# lcd20x4_right.net
KiCad netlist of a schematic drawn in EAGLE
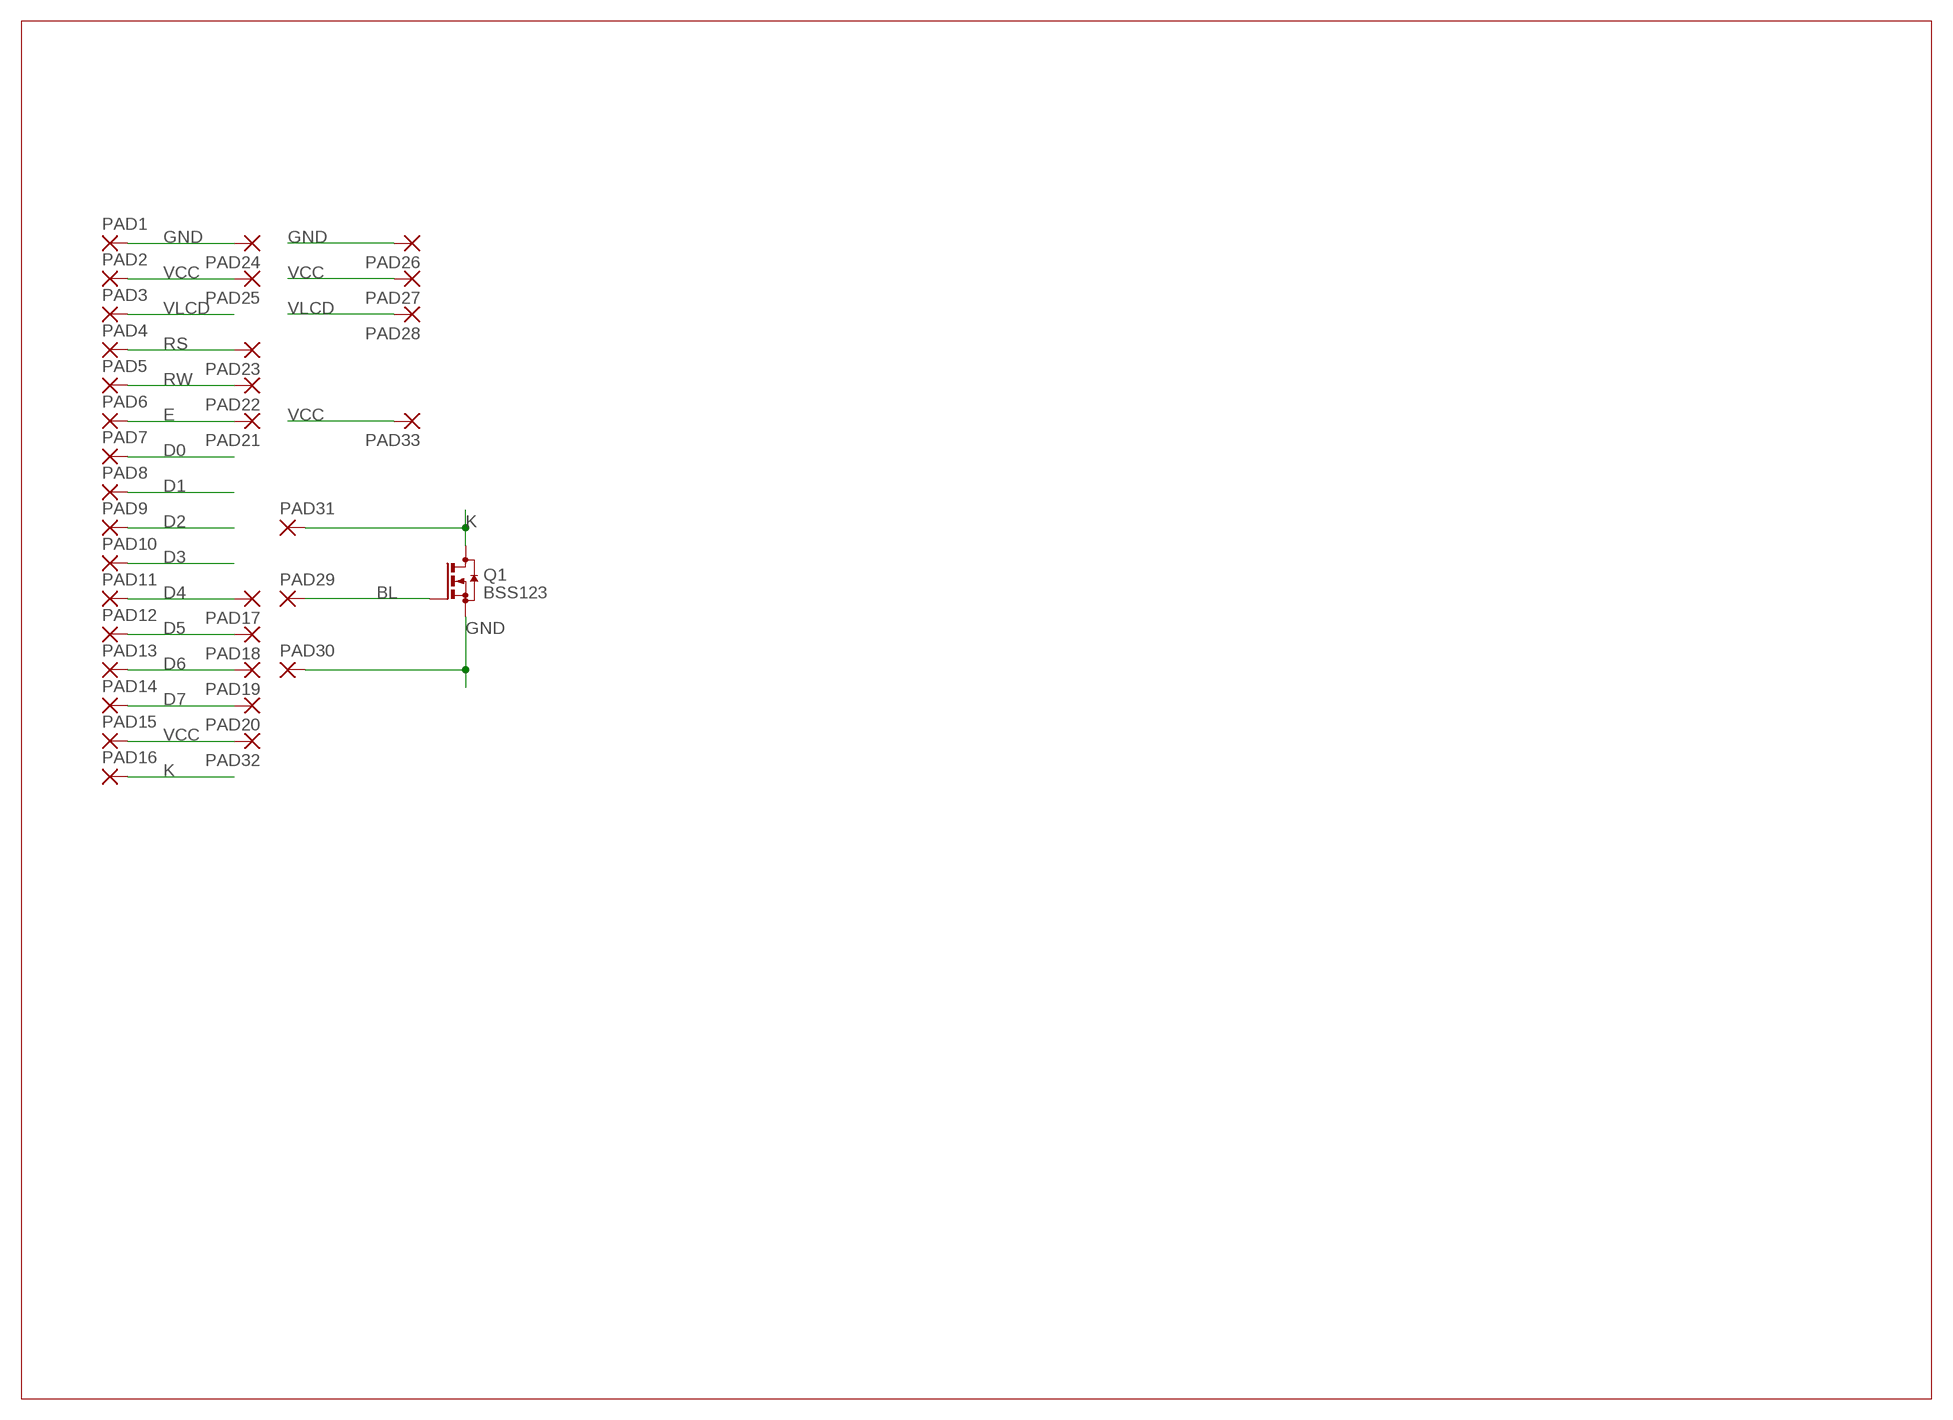
[diagram p0: schematic, sheet 1]

(export (version "E")
  (design (tool "Eeschema 10.0.6"))
  (components
    (comp (ref "PAD1")
      (value "WIREPAD1,6/0,8")
      (footprint "eagle-import:1,6_0,8")
      (libsource (lib "eagle-import") (part "WIREPAD1,6/0,8"))
    )
    (comp (ref "PAD2")
      (value "WIREPAD1,6/0,8")
      (footprint "eagle-import:1,6_0,8")
      (libsource (lib "eagle-import") (part "WIREPAD1,6/0,8"))
    )
    (comp (ref "PAD3")
      (value "WIREPAD1,6/0,8")
      (footprint "eagle-import:1,6_0,8")
      (libsource (lib "eagle-import") (part "WIREPAD1,6/0,8"))
    )
    (comp (ref "PAD4")
      (value "WIREPAD1,6/0,8")
      (footprint "eagle-import:1,6_0,8")
      (libsource (lib "eagle-import") (part "WIREPAD1,6/0,8"))
    )
    (comp (ref "PAD5")
      (value "WIREPAD1,6/0,8")
      (footprint "eagle-import:1,6_0,8")
      (libsource (lib "eagle-import") (part "WIREPAD1,6/0,8"))
    )
    (comp (ref "PAD6")
      (value "WIREPAD1,6/0,8")
      (footprint "eagle-import:1,6_0,8")
      (libsource (lib "eagle-import") (part "WIREPAD1,6/0,8"))
    )
    (comp (ref "PAD7")
      (value "WIREPAD1,6/0,8")
      (footprint "eagle-import:1,6_0,8")
      (libsource (lib "eagle-import") (part "WIREPAD1,6/0,8"))
    )
    (comp (ref "PAD8")
      (value "WIREPAD1,6/0,8")
      (footprint "eagle-import:1,6_0,8")
      (libsource (lib "eagle-import") (part "WIREPAD1,6/0,8"))
    )
    (comp (ref "PAD9")
      (value "WIREPAD1,6/0,8")
      (footprint "eagle-import:1,6_0,8")
      (libsource (lib "eagle-import") (part "WIREPAD1,6/0,8"))
    )
    (comp (ref "PAD10")
      (value "WIREPAD1,6/0,8")
      (footprint "eagle-import:1,6_0,8")
      (libsource (lib "eagle-import") (part "WIREPAD1,6/0,8"))
    )
    (comp (ref "PAD11")
      (value "WIREPAD1,6/0,8")
      (footprint "eagle-import:1,6_0,8")
      (libsource (lib "eagle-import") (part "WIREPAD1,6/0,8"))
    )
    (comp (ref "PAD12")
      (value "WIREPAD1,6/0,8")
      (footprint "eagle-import:1,6_0,8")
      (libsource (lib "eagle-import") (part "WIREPAD1,6/0,8"))
    )
    (comp (ref "PAD13")
      (value "WIREPAD1,6/0,8")
      (footprint "eagle-import:1,6_0,8")
      (libsource (lib "eagle-import") (part "WIREPAD1,6/0,8"))
    )
    (comp (ref "PAD14")
      (value "WIREPAD1,6/0,8")
      (footprint "eagle-import:1,6_0,8")
      (libsource (lib "eagle-import") (part "WIREPAD1,6/0,8"))
    )
    (comp (ref "PAD15")
      (value "WIREPAD1,6/0,8")
      (footprint "eagle-import:1,6_0,8")
      (libsource (lib "eagle-import") (part "WIREPAD1,6/0,8"))
    )
    (comp (ref "PAD16")
      (value "WIREPAD1,6/0,8")
      (footprint "eagle-import:1,6_0,8")
      (libsource (lib "eagle-import") (part "WIREPAD1,6/0,8"))
    )
    (comp (ref "PAD17")
      (value "WIREPAD1,6/0,8")
      (footprint "eagle-import:1,6_0,8")
      (libsource (lib "eagle-import") (part "WIREPAD1,6/0,8"))
    )
    (comp (ref "PAD18")
      (value "WIREPAD1,6/0,8")
      (footprint "eagle-import:1,6_0,8")
      (libsource (lib "eagle-import") (part "WIREPAD1,6/0,8"))
    )
    (comp (ref "PAD19")
      (value "WIREPAD1,6/0,8")
      (footprint "eagle-import:1,6_0,8")
      (libsource (lib "eagle-import") (part "WIREPAD1,6/0,8"))
    )
    (comp (ref "PAD20")
      (value "WIREPAD1,6/0,8")
      (footprint "eagle-import:1,6_0,8")
      (libsource (lib "eagle-import") (part "WIREPAD1,6/0,8"))
    )
    (comp (ref "PAD21")
      (value "WIREPAD1,6/0,8")
      (footprint "eagle-import:1,6_0,8")
      (libsource (lib "eagle-import") (part "WIREPAD1,6/0,8"))
    )
    (comp (ref "PAD22")
      (value "WIREPAD1,6/0,8")
      (footprint "eagle-import:1,6_0,8")
      (libsource (lib "eagle-import") (part "WIREPAD1,6/0,8"))
    )
    (comp (ref "PAD23")
      (value "WIREPAD1,6/0,8")
      (footprint "eagle-import:1,6_0,8")
      (libsource (lib "eagle-import") (part "WIREPAD1,6/0,8"))
    )
    (comp (ref "PAD24")
      (value "WIREPAD1,6/0,8")
      (footprint "eagle-import:1,6_0,8")
      (libsource (lib "eagle-import") (part "WIREPAD1,6/0,8"))
    )
    (comp (ref "PAD25")
      (value "WIREPAD1,6/0,8")
      (footprint "eagle-import:1,6_0,8")
      (libsource (lib "eagle-import") (part "WIREPAD1,6/0,8"))
    )
    (comp (ref "PAD26")
      (value "WIREPAD1,6/0,8")
      (footprint "eagle-import:1,6_0,8")
      (libsource (lib "eagle-import") (part "WIREPAD1,6/0,8"))
    )
    (comp (ref "PAD27")
      (value "WIREPAD1,6/0,8")
      (footprint "eagle-import:1,6_0,8")
      (libsource (lib "eagle-import") (part "WIREPAD1,6/0,8"))
    )
    (comp (ref "PAD28")
      (value "WIREPAD1,6/0,8")
      (footprint "eagle-import:1,6_0,8")
      (libsource (lib "eagle-import") (part "WIREPAD1,6/0,8"))
    )
    (comp (ref "PAD29")
      (value "WIREPAD1,6/0,8")
      (footprint "eagle-import:1,6_0,8")
      (libsource (lib "eagle-import") (part "WIREPAD1,6/0,8"))
    )
    (comp (ref "PAD30")
      (value "WIREPAD1,6/0,8")
      (footprint "eagle-import:1,6_0,8")
      (libsource (lib "eagle-import") (part "WIREPAD1,6/0,8"))
    )
    (comp (ref "PAD31")
      (value "WIREPAD1,6/0,8")
      (footprint "eagle-import:1,6_0,8")
      (libsource (lib "eagle-import") (part "WIREPAD1,6/0,8"))
    )
    (comp (ref "PAD32")
      (value "WIREPAD1,6/0,8")
      (footprint "eagle-import:1,6_0,8")
      (libsource (lib "eagle-import") (part "WIREPAD1,6/0,8"))
    )
    (comp (ref "PAD33")
      (value "WIREPAD1,6/0,8")
      (footprint "eagle-import:1,6_0,8")
      (libsource (lib "eagle-import") (part "WIREPAD1,6/0,8"))
    )
    (comp (ref "Q1")
      (value "BSS123")
      (footprint "eagle-import:SOT23")
      (libsource (lib "eagle-import") (part "BSS123"))
    )
  )
  (nets
    (net (code "1") (name "/BL") (class "Default")
      (node (ref "PAD29") (pin "1") (pinfunction "P_1") (pintype "passive"))
      (node (ref "Q1") (pin "1") (pinfunction "G_1") (pintype "passive"))
    )
    (net (code "2") (name "/D0") (class "Default")
      (node (ref "PAD7") (pin "1") (pinfunction "P_1") (pintype "passive"))
    )
    (net (code "3") (name "/D1") (class "Default")
      (node (ref "PAD8") (pin "1") (pinfunction "P_1") (pintype "passive"))
    )
    (net (code "4") (name "/D2") (class "Default")
      (node (ref "PAD9") (pin "1") (pinfunction "P_1") (pintype "passive"))
    )
    (net (code "5") (name "/D3") (class "Default")
      (node (ref "PAD10") (pin "1") (pinfunction "P_1") (pintype "passive"))
    )
    (net (code "6") (name "/D4") (class "Default")
      (node (ref "PAD11") (pin "1") (pinfunction "P_1") (pintype "passive"))
      (node (ref "PAD17") (pin "1") (pinfunction "P_1") (pintype "passive"))
    )
    (net (code "7") (name "/D5") (class "Default")
      (node (ref "PAD12") (pin "1") (pinfunction "P_1") (pintype "passive"))
      (node (ref "PAD18") (pin "1") (pinfunction "P_1") (pintype "passive"))
    )
    (net (code "8") (name "/D6") (class "Default")
      (node (ref "PAD13") (pin "1") (pinfunction "P_1") (pintype "passive"))
      (node (ref "PAD19") (pin "1") (pinfunction "P_1") (pintype "passive"))
    )
    (net (code "9") (name "/D7") (class "Default")
      (node (ref "PAD14") (pin "1") (pinfunction "P_1") (pintype "passive"))
      (node (ref "PAD20") (pin "1") (pinfunction "P_1") (pintype "passive"))
    )
    (net (code "10") (name "/E") (class "Default")
      (node (ref "PAD21") (pin "1") (pinfunction "P_1") (pintype "passive"))
      (node (ref "PAD6") (pin "1") (pinfunction "P_1") (pintype "passive"))
    )
    (net (code "11") (name "/GND") (class "Default")
      (node (ref "PAD1") (pin "1") (pinfunction "P_1") (pintype "passive"))
      (node (ref "PAD24") (pin "1") (pinfunction "P_1") (pintype "passive"))
      (node (ref "PAD26") (pin "1") (pinfunction "P_1") (pintype "passive"))
      (node (ref "PAD30") (pin "1") (pinfunction "P_1") (pintype "passive"))
      (node (ref "Q1") (pin "2") (pinfunction "S_2") (pintype "passive"))
    )
    (net (code "12") (name "/K") (class "Default")
      (node (ref "PAD16") (pin "1") (pinfunction "P_1") (pintype "passive"))
      (node (ref "PAD31") (pin "1") (pinfunction "P_1") (pintype "passive"))
      (node (ref "Q1") (pin "3") (pinfunction "D_3") (pintype "passive"))
    )
    (net (code "13") (name "/RS") (class "Default")
      (node (ref "PAD23") (pin "1") (pinfunction "P_1") (pintype "passive"))
      (node (ref "PAD4") (pin "1") (pinfunction "P_1") (pintype "passive"))
    )
    (net (code "14") (name "/RW") (class "Default")
      (node (ref "PAD22") (pin "1") (pinfunction "P_1") (pintype "passive"))
      (node (ref "PAD5") (pin "1") (pinfunction "P_1") (pintype "passive"))
    )
    (net (code "15") (name "/VCC") (class "Default")
      (node (ref "PAD15") (pin "1") (pinfunction "P_1") (pintype "passive"))
      (node (ref "PAD2") (pin "1") (pinfunction "P_1") (pintype "passive"))
      (node (ref "PAD25") (pin "1") (pinfunction "P_1") (pintype "passive"))
      (node (ref "PAD27") (pin "1") (pinfunction "P_1") (pintype "passive"))
      (node (ref "PAD32") (pin "1") (pinfunction "P_1") (pintype "passive"))
      (node (ref "PAD33") (pin "1") (pinfunction "P_1") (pintype "passive"))
    )
    (net (code "16") (name "/VLCD") (class "Default")
      (node (ref "PAD28") (pin "1") (pinfunction "P_1") (pintype "passive"))
      (node (ref "PAD3") (pin "1") (pinfunction "P_1") (pintype "passive"))
    )
  )
)
